# L1Demoscene.net
KiCad netlist of a schematic drawn in EAGLE
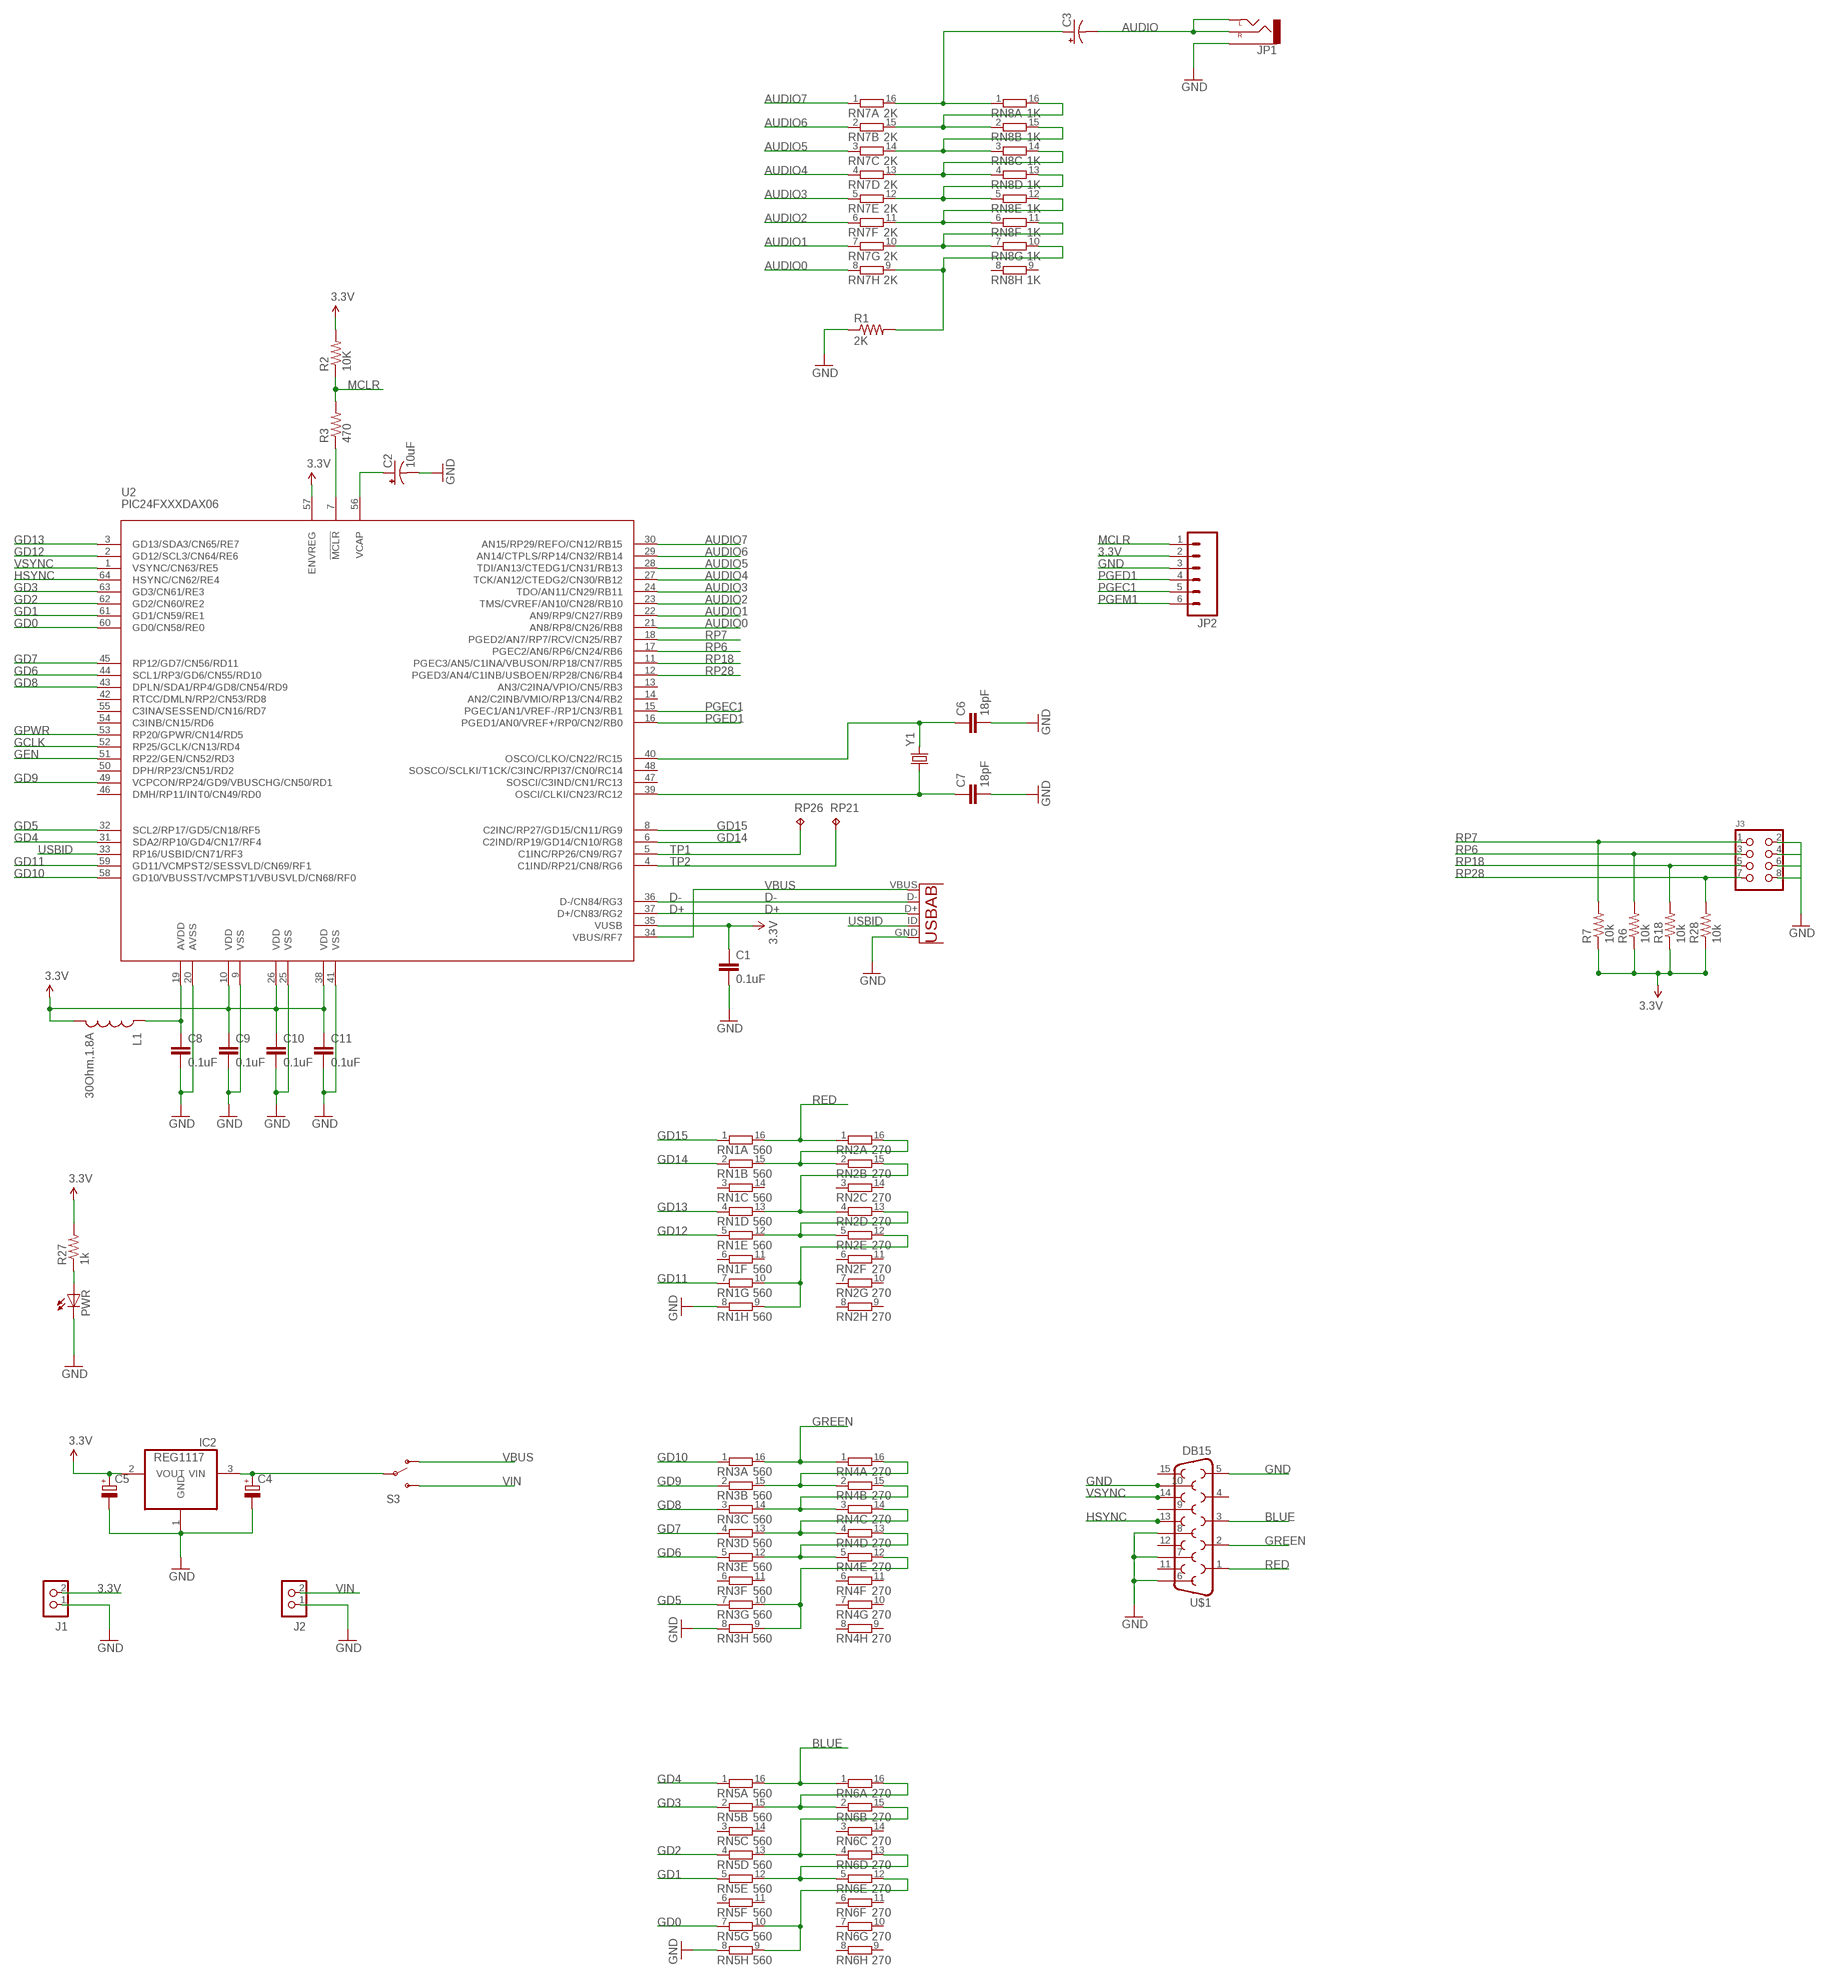
[diagram p0: schematic, sheet 1]

(export (version "E")
  (design (tool "Eeschema 10.0.6"))
  (components
    (comp (ref "C1")
      (value "0.1uF")
      (footprint "eagle-import:0603-CAP")
      (libsource (lib "eagle-import") (part "CAP0603-CAP"))
    )
    (comp (ref "C2")
      (value "10uF")
      (footprint "eagle-import:EIA3216")
      (libsource (lib "eagle-import") (part "CAP_POL1206"))
    )
    (comp (ref "C3")
      (value "CAP_POL1206")
      (footprint "eagle-import:EIA3216")
      (libsource (lib "eagle-import") (part "CAP_POL1206"))
    )
    (comp (ref "C4")
      (value "CAPACITOR_POL-SMC_A")
      (footprint "eagle-import:SMC_A")
      (libsource (lib "eagle-import") (part "CAPACITOR_POL-SMC_A"))
    )
    (comp (ref "C5")
      (value "CAPACITOR_POL-SMC_A")
      (footprint "eagle-import:SMC_A")
      (libsource (lib "eagle-import") (part "CAPACITOR_POL-SMC_A"))
    )
    (comp (ref "C6")
      (value "18pF")
      (footprint "eagle-import:0603-CAP")
      (libsource (lib "eagle-import") (part "CAP0603-CAP"))
    )
    (comp (ref "C7")
      (value "18pF")
      (footprint "eagle-import:0603-CAP")
      (libsource (lib "eagle-import") (part "CAP0603-CAP"))
    )
    (comp (ref "C8")
      (value "0.1uF")
      (footprint "eagle-import:0603-CAP")
      (libsource (lib "eagle-import") (part "CAP0603-CAP"))
    )
    (comp (ref "C9")
      (value "0.1uF")
      (footprint "eagle-import:0603-CAP")
      (libsource (lib "eagle-import") (part "CAP0603-CAP"))
    )
    (comp (ref "C10")
      (value "0.1uF")
      (footprint "eagle-import:0603-CAP")
      (libsource (lib "eagle-import") (part "CAP0603-CAP"))
    )
    (comp (ref "C11")
      (value "0.1uF")
      (footprint "eagle-import:0603-CAP")
      (libsource (lib "eagle-import") (part "CAP0603-CAP"))
    )
    (comp (ref "IC2")
      (value "REG1117")
      (footprint "eagle-import:SOT223")
      (libsource (lib "eagle-import") (part "REG1117"))
    )
    (comp (ref "J1")
      (value "CON_HEADER_1X02-PTH")
      (footprint "eagle-import:M1X2")
      (libsource (lib "eagle-import") (part "CON_HEADER_1X02-PTH"))
    )
    (comp (ref "J2")
      (value "CON_HEADER_1X02-PTH")
      (footprint "eagle-import:M1X2")
      (libsource (lib "eagle-import") (part "CON_HEADER_1X02-PTH"))
    )
    (comp (ref "J3")
      (value "CON_HEADER_2X04-PTH")
      (footprint "eagle-import:M2X4")
      (libsource (lib "eagle-import") (part "CON_HEADER_2X04-PTH"))
    )
    (comp (ref "JP1")
      (value "AUDIO-JACKPTH")
      (footprint "eagle-import:AUDIO-JACK")
      (libsource (lib "eagle-import") (part "AUDIO-JACKPTH"))
    )
    (comp (ref "JP2")
      (value "M06SIP")
      (footprint "eagle-import:1X06")
      (libsource (lib "eagle-import") (part "M06SIP"))
    )
    (comp (ref "L1")
      (value "30Ohm,1.8A")
      (footprint "eagle-import:C0402")
      (libsource (lib "eagle-import") (part "INDUCTOR0402"))
    )
    (comp (ref "PWR")
      (value "LED-0603")
      (footprint "eagle-import:LED-603")
      (libsource (lib "eagle-import") (part "LED-0603"))
    )
    (comp (ref "R1")
      (value "2K")
      (footprint "eagle-import:0603-RES")
      (libsource (lib "eagle-import") (part "RESISTOR0603-RES"))
    )
    (comp (ref "R2")
      (value "10K")
      (footprint "eagle-import:0603-RES")
      (libsource (lib "eagle-import") (part "RESISTOR0603-RES"))
    )
    (comp (ref "R3")
      (value "470")
      (footprint "eagle-import:0603-RES")
      (libsource (lib "eagle-import") (part "RESISTOR0603-RES"))
    )
    (comp (ref "R6")
      (value "10k")
      (footprint "eagle-import:0603-RES")
      (libsource (lib "eagle-import") (part "RESISTOR0603-RES"))
    )
    (comp (ref "R7")
      (value "10k")
      (footprint "eagle-import:0603-RES")
      (libsource (lib "eagle-import") (part "RESISTOR0603-RES"))
    )
    (comp (ref "R18")
      (value "10k")
      (footprint "eagle-import:0603-RES")
      (libsource (lib "eagle-import") (part "RESISTOR0603-RES"))
    )
    (comp (ref "R27")
      (value "1k")
      (footprint "eagle-import:0603-RES")
      (libsource (lib "eagle-import") (part "RESISTOR0603-RES"))
    )
    (comp (ref "R28")
      (value "10k")
      (footprint "eagle-import:0603-RES")
      (libsource (lib "eagle-import") (part "RESISTOR0603-RES"))
    )
    (comp (ref "RN1")
      (value "560")
      (footprint "eagle-import:EXB2HV")
      (libsource (lib "eagle-import") (part "8R-NEXB2HV"))
    )
    (comp (ref "RN2")
      (value "270")
      (footprint "eagle-import:EXB2HV")
      (libsource (lib "eagle-import") (part "8R-NEXB2HV"))
    )
    (comp (ref "RN3")
      (value "560")
      (footprint "eagle-import:EXB2HV")
      (libsource (lib "eagle-import") (part "8R-NEXB2HV"))
    )
    (comp (ref "RN4")
      (value "270")
      (footprint "eagle-import:EXB2HV")
      (libsource (lib "eagle-import") (part "8R-NEXB2HV"))
    )
    (comp (ref "RN5")
      (value "560")
      (footprint "eagle-import:EXB2HV")
      (libsource (lib "eagle-import") (part "8R-NEXB2HV"))
    )
    (comp (ref "RN6")
      (value "270")
      (footprint "eagle-import:EXB2HV")
      (libsource (lib "eagle-import") (part "8R-NEXB2HV"))
    )
    (comp (ref "RN7")
      (value "2K")
      (footprint "eagle-import:EXB2HV")
      (libsource (lib "eagle-import") (part "8R-NEXB2HV"))
    )
    (comp (ref "RN8")
      (value "1K")
      (footprint "eagle-import:EXB2HV")
      (libsource (lib "eagle-import") (part "8R-NEXB2HV"))
    )
    (comp (ref "RP21")
      (value "TPTP06R")
      (footprint "eagle-import:TP06R")
      (libsource (lib "eagle-import") (part "TPTP06R"))
    )
    (comp (ref "RP26")
      (value "TPTP06R")
      (footprint "eagle-import:TP06R")
      (libsource (lib "eagle-import") (part "TPTP06R"))
    )
    (comp (ref "S3")
      (value "SWITCH-SPDT-SMD-A")
      (footprint "eagle-import:SWITCH-SPST-SMD-A")
      (libsource (lib "eagle-import") (part "SWITCH-SPDT-SMD-A"))
    )
    (comp (ref "U$1")
      (value "DB15")
      (footprint "eagle-import:DB15")
      (libsource (lib "eagle-import") (part "DB15"))
    )
    (comp (ref "U2")
      (value "PIC24FXXXDAX06")
      (footprint "eagle-import:PIC24FXXX_TQFP64")
      (libsource (lib "eagle-import") (part "PIC24FXXXDAX06"))
    )
    (comp (ref "U3")
      (value "USB-AB")
      (footprint "eagle-import:USB-AB-MICRO-SMD")
      (libsource (lib "eagle-import") (part "USB-AB"))
    )
    (comp (ref "Y1")
      (value "CRYSTAL5X3")
      (footprint "eagle-import:CRYSTAL-SMD-5X3")
      (libsource (lib "eagle-import") (part "CRYSTAL5X3"))
    )
  )
  (nets
    (net (code "1") (name "/AUDIO") (class "Default")
      (node (ref "C3") (pin "C") (pinfunction "-_C") (pintype "passive"))
      (node (ref "JP1") (pin "RING") (pinfunction "RIGHT_RING") (pintype "bidirectional"))
      (node (ref "JP1") (pin "TIP") (pinfunction "LEFT_TIP") (pintype "bidirectional"))
    )
    (net (code "2") (name "/AUDIO0") (class "Default")
      (node (ref "RN7") (pin "8") (pinfunction "1_8") (pintype "passive"))
      (node (ref "U2") (pin "21") (pinfunction "AN8/RP8/CN26/RB8_21") (pintype "bidirectional"))
    )
    (net (code "3") (name "/AUDIO1") (class "Default")
      (node (ref "RN7") (pin "7") (pinfunction "1_7") (pintype "passive"))
      (node (ref "U2") (pin "22") (pinfunction "AN9/RP9/CN27/RB9_22") (pintype "bidirectional"))
    )
    (net (code "4") (name "/AUDIO2") (class "Default")
      (node (ref "RN7") (pin "6") (pinfunction "1_6") (pintype "passive"))
      (node (ref "U2") (pin "23") (pinfunction "TMS/CVREF/AN10/CN28/RB10_23") (pintype "bidirectional"))
    )
    (net (code "5") (name "/AUDIO3") (class "Default")
      (node (ref "RN7") (pin "5") (pinfunction "1_5") (pintype "passive"))
      (node (ref "U2") (pin "24") (pinfunction "TDO/AN11/CN29/RB11_24") (pintype "bidirectional"))
    )
    (net (code "6") (name "/AUDIO4") (class "Default")
      (node (ref "RN7") (pin "4") (pinfunction "1_4") (pintype "passive"))
      (node (ref "U2") (pin "27") (pinfunction "TCK/AN12/CTEDG2/CN30/RB12_27") (pintype "bidirectional"))
    )
    (net (code "7") (name "/AUDIO5") (class "Default")
      (node (ref "RN7") (pin "3") (pinfunction "1_3") (pintype "passive"))
      (node (ref "U2") (pin "28") (pinfunction "TDI/AN13/CTEDG1/CN31/RB13_28") (pintype "bidirectional"))
    )
    (net (code "8") (name "/AUDIO6") (class "Default")
      (node (ref "RN7") (pin "2") (pinfunction "1_2") (pintype "passive"))
      (node (ref "U2") (pin "29") (pinfunction "AN14/CTPLS/RP14/CN32/RB14_29") (pintype "bidirectional"))
    )
    (net (code "9") (name "/AUDIO7") (class "Default")
      (node (ref "RN7") (pin "1") (pinfunction "1_1") (pintype "passive"))
      (node (ref "U2") (pin "30") (pinfunction "AN15/RP29/REFO/CN12/RB15_30") (pintype "bidirectional"))
    )
    (net (code "10") (name "/BLUE") (class "Default")
      (node (ref "RN5") (pin "16") (pinfunction "2_16") (pintype "passive"))
      (node (ref "RN6") (pin "1") (pinfunction "1_1") (pintype "passive"))
      (node (ref "U$1") (pin "3") (pinfunction "3_3") (pintype "passive"))
    )
    (net (code "11") (name "/D+") (class "Default")
      (node (ref "U2") (pin "37") (pinfunction "D+/CN83/RG2_37") (pintype "bidirectional"))
      (node (ref "U3") (pin "D+") (pinfunction "D+_D+") (pintype "bidirectional"))
    )
    (net (code "12") (name "/D-") (class "Default")
      (node (ref "U2") (pin "36") (pinfunction "D-/CN84/RG3_36") (pintype "bidirectional"))
      (node (ref "U3") (pin "D-") (pinfunction "D-_D-") (pintype "bidirectional"))
    )
    (net (code "13") (name "/GCLK") (class "Default")
      (node (ref "U2") (pin "52") (pinfunction "RP25/GCLK/CN13/RD4_52") (pintype "bidirectional"))
    )
    (net (code "14") (name "/GD0") (class "Default")
      (node (ref "RN5") (pin "7") (pinfunction "1_7") (pintype "passive"))
      (node (ref "U2") (pin "60") (pinfunction "GD0/CN58/RE0_60") (pintype "bidirectional"))
    )
    (net (code "15") (name "/GD1") (class "Default")
      (node (ref "RN5") (pin "5") (pinfunction "1_5") (pintype "passive"))
      (node (ref "U2") (pin "61") (pinfunction "GD1/CN59/RE1_61") (pintype "bidirectional"))
    )
    (net (code "16") (name "/GD2") (class "Default")
      (node (ref "RN5") (pin "4") (pinfunction "1_4") (pintype "passive"))
      (node (ref "U2") (pin "62") (pinfunction "GD2/CN60/RE2_62") (pintype "bidirectional"))
    )
    (net (code "17") (name "/GD3") (class "Default")
      (node (ref "RN5") (pin "2") (pinfunction "1_2") (pintype "passive"))
      (node (ref "U2") (pin "63") (pinfunction "GD3/CN61/RE3_63") (pintype "bidirectional"))
    )
    (net (code "18") (name "/GD4") (class "Default")
      (node (ref "RN5") (pin "1") (pinfunction "1_1") (pintype "passive"))
      (node (ref "U2") (pin "31") (pinfunction "SDA2/RP10/GD4/CN17/RF4_31") (pintype "bidirectional"))
    )
    (net (code "19") (name "/GD5") (class "Default")
      (node (ref "RN3") (pin "7") (pinfunction "1_7") (pintype "passive"))
      (node (ref "U2") (pin "32") (pinfunction "SCL2/RP17/GD5/CN18/RF5_32") (pintype "bidirectional"))
    )
    (net (code "20") (name "/GD6") (class "Default")
      (node (ref "RN3") (pin "5") (pinfunction "1_5") (pintype "passive"))
      (node (ref "U2") (pin "44") (pinfunction "SCL1/RP3/GD6/CN55/RD10_44") (pintype "bidirectional"))
    )
    (net (code "21") (name "/GD7") (class "Default")
      (node (ref "RN3") (pin "4") (pinfunction "1_4") (pintype "passive"))
      (node (ref "U2") (pin "45") (pinfunction "RP12/GD7/CN56/RD11_45") (pintype "bidirectional"))
    )
    (net (code "22") (name "/GD8") (class "Default")
      (node (ref "RN3") (pin "3") (pinfunction "1_3") (pintype "passive"))
      (node (ref "U2") (pin "43") (pinfunction "DPLN/SDA1/RP4/GD8/CN54/RD9_43") (pintype "bidirectional"))
    )
    (net (code "23") (name "/GD9") (class "Default")
      (node (ref "RN3") (pin "2") (pinfunction "1_2") (pintype "passive"))
      (node (ref "U2") (pin "49") (pinfunction "VCPCON/RP24/GD9/VBUSCHG/CN50/RD1_49") (pintype "bidirectional"))
    )
    (net (code "24") (name "/GD10") (class "Default")
      (node (ref "RN3") (pin "1") (pinfunction "1_1") (pintype "passive"))
      (node (ref "U2") (pin "58") (pinfunction "GD10/VBUSST/VCMPST1/VBUSVLD/CN68/RF0_58") (pintype "bidirectional"))
    )
    (net (code "25") (name "/GD11") (class "Default")
      (node (ref "RN1") (pin "7") (pinfunction "1_7") (pintype "passive"))
      (node (ref "U2") (pin "59") (pinfunction "GD11/VCMPST2/SESSVLD/CN69/RF1_59") (pintype "bidirectional"))
    )
    (net (code "26") (name "/GD12") (class "Default")
      (node (ref "RN1") (pin "5") (pinfunction "1_5") (pintype "passive"))
      (node (ref "U2") (pin "2") (pinfunction "GD12/SCL3/CN64/RE6_2") (pintype "bidirectional"))
    )
    (net (code "27") (name "/GD13") (class "Default")
      (node (ref "RN1") (pin "4") (pinfunction "1_4") (pintype "passive"))
      (node (ref "U2") (pin "3") (pinfunction "GD13/SDA3/CN65/RE7_3") (pintype "bidirectional"))
    )
    (net (code "28") (name "/GD14") (class "Default")
      (node (ref "RN1") (pin "2") (pinfunction "1_2") (pintype "passive"))
      (node (ref "U2") (pin "6") (pinfunction "C2IND/RP19/GD14/CN10/RG8_6") (pintype "bidirectional"))
    )
    (net (code "29") (name "/GD15") (class "Default")
      (node (ref "RN1") (pin "1") (pinfunction "1_1") (pintype "passive"))
      (node (ref "U2") (pin "8") (pinfunction "C2INC/RP27/GD15/CN11/RG9_8") (pintype "bidirectional"))
    )
    (net (code "30") (name "/GEN") (class "Default")
      (node (ref "U2") (pin "51") (pinfunction "RP22/GEN/CN52/RD3_51") (pintype "bidirectional"))
    )
    (net (code "31") (name "/GPWR") (class "Default")
      (node (ref "U2") (pin "53") (pinfunction "RP20/GPWR/CN14/RD5_53") (pintype "bidirectional"))
    )
    (net (code "32") (name "/GREEN") (class "Default")
      (node (ref "RN3") (pin "16") (pinfunction "2_16") (pintype "passive"))
      (node (ref "RN4") (pin "1") (pinfunction "1_1") (pintype "passive"))
      (node (ref "U$1") (pin "2") (pinfunction "2_2") (pintype "passive"))
    )
    (net (code "33") (name "/HSYNC") (class "Default")
      (node (ref "U$1") (pin "13") (pinfunction "13_13") (pintype "passive"))
      (node (ref "U2") (pin "64") (pinfunction "HSYNC/CN62/RE4_64") (pintype "bidirectional"))
    )
    (net (code "34") (name "/MCLR") (class "Default")
      (node (ref "JP2") (pin "1") (pinfunction "1_1") (pintype "passive"))
      (node (ref "R2") (pin "1") (pinfunction "1_1") (pintype "passive"))
      (node (ref "R3") (pin "2") (pinfunction "2_2") (pintype "passive"))
    )
    (net (code "35") (name "/PGEC1") (class "Default")
      (node (ref "JP2") (pin "5") (pinfunction "5_5") (pintype "passive"))
      (node (ref "U2") (pin "15") (pinfunction "PGEC1/AN1/VREF-/RP1/CN3/RB1_15") (pintype "bidirectional"))
    )
    (net (code "36") (name "/PGED1") (class "Default")
      (node (ref "JP2") (pin "4") (pinfunction "4_4") (pintype "passive"))
      (node (ref "U2") (pin "16") (pinfunction "PGED1/AN0/VREF+/RP0/CN2/RB0_16") (pintype "bidirectional"))
    )
    (net (code "37") (name "/PGEM1") (class "Default")
      (node (ref "JP2") (pin "6") (pinfunction "6_6") (pintype "passive"))
    )
    (net (code "38") (name "/RED") (class "Default")
      (node (ref "RN1") (pin "16") (pinfunction "2_16") (pintype "passive"))
      (node (ref "RN2") (pin "1") (pinfunction "1_1") (pintype "passive"))
      (node (ref "U$1") (pin "1") (pinfunction "1_1") (pintype "passive"))
    )
    (net (code "39") (name "/RP6") (class "Default")
      (node (ref "J3") (pin "3") (pinfunction "P$3_3") (pintype "passive"))
      (node (ref "R6") (pin "2") (pinfunction "2_2") (pintype "passive"))
      (node (ref "U2") (pin "17") (pinfunction "PGEC2/AN6/RP6/CN24/RB6_17") (pintype "bidirectional"))
    )
    (net (code "40") (name "/RP7") (class "Default")
      (node (ref "J3") (pin "1") (pinfunction "P$1_1") (pintype "passive"))
      (node (ref "R7") (pin "2") (pinfunction "2_2") (pintype "passive"))
      (node (ref "U2") (pin "18") (pinfunction "PGED2/AN7/RP7/RCV/CN25/RB7_18") (pintype "bidirectional"))
    )
    (net (code "41") (name "/RP18") (class "Default")
      (node (ref "J3") (pin "5") (pinfunction "P$5_5") (pintype "passive"))
      (node (ref "R18") (pin "2") (pinfunction "2_2") (pintype "passive"))
      (node (ref "U2") (pin "11") (pinfunction "PGEC3/AN5/C1INA/VBUSON/RP18/CN7/RB5_11") (pintype "bidirectional"))
    )
    (net (code "42") (name "/RP28") (class "Default")
      (node (ref "J3") (pin "7") (pinfunction "P$7_7") (pintype "passive"))
      (node (ref "R28") (pin "2") (pinfunction "2_2") (pintype "passive"))
      (node (ref "U2") (pin "12") (pinfunction "PGED3/AN4/C1INB/USBOEN/RP28/CN6/RB4_12") (pintype "bidirectional"))
    )
    (net (code "43") (name "/TP1") (class "Default")
      (node (ref "RP26") (pin "TP") (pinfunction "TP_TP") (pintype "input"))
      (node (ref "U2") (pin "5") (pinfunction "C1INC/RP26/CN9/RG7_5") (pintype "bidirectional"))
    )
    (net (code "44") (name "/TP2") (class "Default")
      (node (ref "RP21") (pin "TP") (pinfunction "TP_TP") (pintype "input"))
      (node (ref "U2") (pin "4") (pinfunction "C1IND/RP21/CN8/RG6_4") (pintype "bidirectional"))
    )
    (net (code "45") (name "/USBID") (class "Default")
      (node (ref "U2") (pin "33") (pinfunction "RP16/USBID/CN71/RF3_33") (pintype "bidirectional"))
      (node (ref "U3") (pin "ID") (pinfunction "USBID_ID") (pintype "bidirectional"))
    )
    (net (code "46") (name "/VBUS") (class "Default")
      (node (ref "S3") (pin "1") (pinfunction "O_1") (pintype "passive"))
      (node (ref "U2") (pin "34") (pinfunction "VBUS/RF7_34") (pintype "input"))
      (node (ref "U3") (pin "VBUS") (pinfunction "VBUS_VBUS") (pintype "bidirectional"))
    )
    (net (code "47") (name "/VIN") (class "Default")
      (node (ref "J2") (pin "2") (pinfunction "2_2") (pintype "passive"))
      (node (ref "S3") (pin "3") (pinfunction "S_3") (pintype "passive"))
    )
    (net (code "48") (name "/VSYNC") (class "Default")
      (node (ref "U$1") (pin "14") (pinfunction "14_14") (pintype "passive"))
      (node (ref "U2") (pin "1") (pinfunction "VSYNC/CN63/RE5_1") (pintype "bidirectional"))
    )
    (net (code "49") (name "3.3V") (class "Default")
      (node (ref "C1") (pin "1") (pinfunction "1_1") (pintype "passive"))
      (node (ref "C10") (pin "1") (pinfunction "1_1") (pintype "passive"))
      (node (ref "C11") (pin "1") (pinfunction "1_1") (pintype "passive"))
      (node (ref "C5") (pin "+") (pinfunction "+_+") (pintype "passive"))
      (node (ref "C9") (pin "1") (pinfunction "1_1") (pintype "passive"))
      (node (ref "IC2") (pin "2") (pinfunction "VOUT_2") (pintype "output"))
      (node (ref "J1") (pin "2") (pinfunction "2_2") (pintype "passive"))
      (node (ref "JP2") (pin "2") (pinfunction "2_2") (pintype "passive"))
      (node (ref "L1") (pin "2") (pinfunction "2_2") (pintype "passive"))
      (node (ref "R18") (pin "1") (pinfunction "1_1") (pintype "passive"))
      (node (ref "R2") (pin "2") (pinfunction "2_2") (pintype "passive"))
      (node (ref "R27") (pin "2") (pinfunction "2_2") (pintype "passive"))
      (node (ref "R28") (pin "1") (pinfunction "1_1") (pintype "passive"))
      (node (ref "R6") (pin "1") (pinfunction "1_1") (pintype "passive"))
      (node (ref "R7") (pin "1") (pinfunction "1_1") (pintype "passive"))
      (node (ref "U2") (pin "10") (pinfunction "VDD_10") (pintype "power_in"))
      (node (ref "U2") (pin "26") (pinfunction "VDD_26") (pintype "power_in"))
      (node (ref "U2") (pin "35") (pinfunction "VUSB_35") (pintype "power_in"))
      (node (ref "U2") (pin "38") (pinfunction "VDD_38") (pintype "power_in"))
      (node (ref "U2") (pin "57") (pinfunction "ENVREG_57") (pintype "input"))
    )
    (net (code "50") (name "GND") (class "Default")
      (node (ref "C1") (pin "2") (pinfunction "2_2") (pintype "passive"))
      (node (ref "C10") (pin "2") (pinfunction "2_2") (pintype "passive"))
      (node (ref "C11") (pin "2") (pinfunction "2_2") (pintype "passive"))
      (node (ref "C2") (pin "C") (pinfunction "-_C") (pintype "passive"))
      (node (ref "C4") (pin "-") (pinfunction "-_-") (pintype "passive"))
      (node (ref "C5") (pin "-") (pinfunction "-_-") (pintype "passive"))
      (node (ref "C6") (pin "2") (pinfunction "2_2") (pintype "passive"))
      (node (ref "C7") (pin "2") (pinfunction "2_2") (pintype "passive"))
      (node (ref "C8") (pin "2") (pinfunction "2_2") (pintype "passive"))
      (node (ref "C9") (pin "2") (pinfunction "2_2") (pintype "passive"))
      (node (ref "IC2") (pin "1") (pinfunction "GND_1") (pintype "power_in"))
      (node (ref "J1") (pin "1") (pinfunction "1_1") (pintype "passive"))
      (node (ref "J2") (pin "1") (pinfunction "1_1") (pintype "passive"))
      (node (ref "J3") (pin "2") (pinfunction "P$2_2") (pintype "passive"))
      (node (ref "J3") (pin "4") (pinfunction "P$4_4") (pintype "passive"))
      (node (ref "J3") (pin "6") (pinfunction "P$6_6") (pintype "passive"))
      (node (ref "J3") (pin "8") (pinfunction "P$8_8") (pintype "passive"))
      (node (ref "JP1") (pin "SLEEVE") (pinfunction "SLEEVE_SLEEVE") (pintype "bidirectional"))
      (node (ref "JP2") (pin "3") (pinfunction "3_3") (pintype "passive"))
      (node (ref "PWR") (pin "C") (pinfunction "C_C") (pintype "passive"))
      (node (ref "R1") (pin "1") (pinfunction "1_1") (pintype "passive"))
      (node (ref "RN1") (pin "8") (pinfunction "1_8") (pintype "passive"))
      (node (ref "RN3") (pin "8") (pinfunction "1_8") (pintype "passive"))
      (node (ref "RN5") (pin "8") (pinfunction "1_8") (pintype "passive"))
      (node (ref "U$1") (pin "10") (pinfunction "10_10") (pintype "passive"))
      (node (ref "U$1") (pin "5") (pinfunction "5_5") (pintype "passive"))
      (node (ref "U$1") (pin "6") (pinfunction "6_6") (pintype "passive"))
      (node (ref "U$1") (pin "7") (pinfunction "7_7") (pintype "passive"))
      (node (ref "U$1") (pin "8") (pinfunction "8_8") (pintype "passive"))
      (node (ref "U2") (pin "20") (pinfunction "AVSS_20") (pintype "power_in"))
      (node (ref "U2") (pin "25") (pinfunction "VSS_25") (pintype "power_in"))
      (node (ref "U2") (pin "41") (pinfunction "VSS_41") (pintype "power_in"))
      (node (ref "U2") (pin "9") (pinfunction "VSS_9") (pintype "power_in"))
      (node (ref "U3") (pin "GND") (pinfunction "GND_GND") (pintype "bidirectional"))
    )
    (net (code "51") (name "Net-(C2-+)") (class "Default")
      (node (ref "C2") (pin "A") (pinfunction "+_A") (pintype "passive"))
      (node (ref "U2") (pin "56") (pinfunction "VCAP_56") (pintype "power_in"))
    )
    (net (code "52") (name "Net-(C3-+)") (class "Default")
      (node (ref "C3") (pin "A") (pinfunction "+_A") (pintype "passive"))
      (node (ref "RN7") (pin "16") (pinfunction "2_16") (pintype "passive"))
      (node (ref "RN8") (pin "1") (pinfunction "1_1") (pintype "passive"))
    )
    (net (code "53") (name "Net-(IC2-VIN)") (class "Default")
      (node (ref "C4") (pin "+") (pinfunction "+_+") (pintype "passive"))
      (node (ref "IC2") (pin "3") (pinfunction "VIN_3") (pintype "input"))
      (node (ref "S3") (pin "2") (pinfunction "P_2") (pintype "passive"))
    )
    (net (code "54") (name "Net-(PWR-PadA)") (class "Default")
      (node (ref "PWR") (pin "A") (pinfunction "A_A") (pintype "passive"))
      (node (ref "R27") (pin "1") (pinfunction "1_1") (pintype "passive"))
    )
    (net (code "55") (name "Net-(RN1B-2)") (class "Default")
      (node (ref "RN1") (pin "15") (pinfunction "2_15") (pintype "passive"))
      (node (ref "RN2") (pin "16") (pinfunction "2_16") (pintype "passive"))
      (node (ref "RN2") (pin "2") (pinfunction "1_2") (pintype "passive"))
    )
    (net (code "56") (name "Net-(RN1D-2)") (class "Default")
      (node (ref "RN1") (pin "13") (pinfunction "2_13") (pintype "passive"))
      (node (ref "RN2") (pin "15") (pinfunction "2_15") (pintype "passive"))
      (node (ref "RN2") (pin "4") (pinfunction "1_4") (pintype "passive"))
    )
    (net (code "57") (name "Net-(RN1E-2)") (class "Default")
      (node (ref "RN1") (pin "12") (pinfunction "2_12") (pintype "passive"))
      (node (ref "RN2") (pin "13") (pinfunction "2_13") (pintype "passive"))
      (node (ref "RN2") (pin "5") (pinfunction "1_5") (pintype "passive"))
    )
    (net (code "58") (name "Net-(RN1G-2)") (class "Default")
      (node (ref "RN1") (pin "10") (pinfunction "2_10") (pintype "passive"))
      (node (ref "RN1") (pin "9") (pinfunction "2_9") (pintype "passive"))
      (node (ref "RN2") (pin "12") (pinfunction "2_12") (pintype "passive"))
    )
    (net (code "59") (name "Net-(RN3B-2)") (class "Default")
      (node (ref "RN3") (pin "15") (pinfunction "2_15") (pintype "passive"))
      (node (ref "RN4") (pin "16") (pinfunction "2_16") (pintype "passive"))
      (node (ref "RN4") (pin "2") (pinfunction "1_2") (pintype "passive"))
    )
    (net (code "60") (name "Net-(RN3C-2)") (class "Default")
      (node (ref "RN3") (pin "14") (pinfunction "2_14") (pintype "passive"))
      (node (ref "RN4") (pin "15") (pinfunction "2_15") (pintype "passive"))
      (node (ref "RN4") (pin "3") (pinfunction "1_3") (pintype "passive"))
    )
    (net (code "61") (name "Net-(RN3D-2)") (class "Default")
      (node (ref "RN3") (pin "13") (pinfunction "2_13") (pintype "passive"))
      (node (ref "RN4") (pin "14") (pinfunction "2_14") (pintype "passive"))
      (node (ref "RN4") (pin "4") (pinfunction "1_4") (pintype "passive"))
    )
    (net (code "62") (name "Net-(RN3E-2)") (class "Default")
      (node (ref "RN3") (pin "12") (pinfunction "2_12") (pintype "passive"))
      (node (ref "RN4") (pin "13") (pinfunction "2_13") (pintype "passive"))
      (node (ref "RN4") (pin "5") (pinfunction "1_5") (pintype "passive"))
    )
    (net (code "63") (name "Net-(RN3G-2)") (class "Default")
      (node (ref "RN3") (pin "10") (pinfunction "2_10") (pintype "passive"))
      (node (ref "RN3") (pin "9") (pinfunction "2_9") (pintype "passive"))
      (node (ref "RN4") (pin "12") (pinfunction "2_12") (pintype "passive"))
    )
    (net (code "64") (name "Net-(RN5B-2)") (class "Default")
      (node (ref "RN5") (pin "15") (pinfunction "2_15") (pintype "passive"))
      (node (ref "RN6") (pin "16") (pinfunction "2_16") (pintype "passive"))
      (node (ref "RN6") (pin "2") (pinfunction "1_2") (pintype "passive"))
    )
    (net (code "65") (name "Net-(RN5D-2)") (class "Default")
      (node (ref "RN5") (pin "13") (pinfunction "2_13") (pintype "passive"))
      (node (ref "RN6") (pin "15") (pinfunction "2_15") (pintype "passive"))
      (node (ref "RN6") (pin "4") (pinfunction "1_4") (pintype "passive"))
    )
    (net (code "66") (name "Net-(RN5E-2)") (class "Default")
      (node (ref "RN5") (pin "12") (pinfunction "2_12") (pintype "passive"))
      (node (ref "RN6") (pin "13") (pinfunction "2_13") (pintype "passive"))
      (node (ref "RN6") (pin "5") (pinfunction "1_5") (pintype "passive"))
    )
    (net (code "67") (name "Net-(RN5G-2)") (class "Default")
      (node (ref "RN5") (pin "10") (pinfunction "2_10") (pintype "passive"))
      (node (ref "RN5") (pin "9") (pinfunction "2_9") (pintype "passive"))
      (node (ref "RN6") (pin "12") (pinfunction "2_12") (pintype "passive"))
    )
    (net (code "68") (name "Net-(RN7B-2)") (class "Default")
      (node (ref "RN7") (pin "15") (pinfunction "2_15") (pintype "passive"))
      (node (ref "RN8") (pin "16") (pinfunction "2_16") (pintype "passive"))
      (node (ref "RN8") (pin "2") (pinfunction "1_2") (pintype "passive"))
    )
    (net (code "69") (name "Net-(RN7C-2)") (class "Default")
      (node (ref "RN7") (pin "14") (pinfunction "2_14") (pintype "passive"))
      (node (ref "RN8") (pin "15") (pinfunction "2_15") (pintype "passive"))
      (node (ref "RN8") (pin "3") (pinfunction "1_3") (pintype "passive"))
    )
    (net (code "70") (name "Net-(RN7D-2)") (class "Default")
      (node (ref "RN7") (pin "13") (pinfunction "2_13") (pintype "passive"))
      (node (ref "RN8") (pin "14") (pinfunction "2_14") (pintype "passive"))
      (node (ref "RN8") (pin "4") (pinfunction "1_4") (pintype "passive"))
    )
    (net (code "71") (name "Net-(RN7E-2)") (class "Default")
      (node (ref "RN7") (pin "12") (pinfunction "2_12") (pintype "passive"))
      (node (ref "RN8") (pin "13") (pinfunction "2_13") (pintype "passive"))
      (node (ref "RN8") (pin "5") (pinfunction "1_5") (pintype "passive"))
    )
    (net (code "72") (name "Net-(RN7F-2)") (class "Default")
      (node (ref "RN7") (pin "11") (pinfunction "2_11") (pintype "passive"))
      (node (ref "RN8") (pin "12") (pinfunction "2_12") (pintype "passive"))
      (node (ref "RN8") (pin "6") (pinfunction "1_6") (pintype "passive"))
    )
    (net (code "73") (name "Net-(RN7G-2)") (class "Default")
      (node (ref "RN7") (pin "10") (pinfunction "2_10") (pintype "passive"))
      (node (ref "RN8") (pin "11") (pinfunction "2_11") (pintype "passive"))
      (node (ref "RN8") (pin "7") (pinfunction "1_7") (pintype "passive"))
    )
    (net (code "74") (name "Net-(RN7H-2)") (class "Default")
      (node (ref "R1") (pin "2") (pinfunction "2_2") (pintype "passive"))
      (node (ref "RN7") (pin "9") (pinfunction "2_9") (pintype "passive"))
      (node (ref "RN8") (pin "10") (pinfunction "2_10") (pintype "passive"))
    )
    (net (code "75") (name "Net-(U2-AVDD)") (class "Default")
      (node (ref "C8") (pin "1") (pinfunction "1_1") (pintype "passive"))
      (node (ref "L1") (pin "1") (pinfunction "1_1") (pintype "passive"))
      (node (ref "U2") (pin "19") (pinfunction "AVDD_19") (pintype "power_in"))
    )
    (net (code "76") (name "Net-(U2-OSCI{slash}CLKI{slash}CN23{slash}RC12)") (class "Default")
      (node (ref "C7") (pin "1") (pinfunction "1_1") (pintype "passive"))
      (node (ref "U2") (pin "39") (pinfunction "OSCI/CLKI/CN23/RC12_39") (pintype "bidirectional"))
      (node (ref "Y1") (pin "1") (pinfunction "1_1") (pintype "passive"))
    )
    (net (code "77") (name "Net-(U2-OSCO{slash}CLKO{slash}CN22{slash}RC15)") (class "Default")
      (node (ref "C6") (pin "1") (pinfunction "1_1") (pintype "passive"))
      (node (ref "U2") (pin "40") (pinfunction "OSCO/CLKO/CN22/RC15_40") (pintype "bidirectional"))
      (node (ref "Y1") (pin "3") (pinfunction "2_3") (pintype "passive"))
    )
    (net (code "78") (name "Net-(U2-~{MCLR})") (class "Default")
      (node (ref "R3") (pin "1") (pinfunction "1_1") (pintype "passive"))
      (node (ref "U2") (pin "7") (pinfunction "~{MCLR}_7") (pintype "input"))
    )
    (net (code "79") (name "unconnected-(RN1C-1-Pad3)") (class "Default")
      (node (ref "RN1") (pin "3") (pinfunction "1_3") (pintype "passive"))
    )
    (net (code "80") (name "unconnected-(RN1C-2-Pad14)") (class "Default")
      (node (ref "RN1") (pin "14") (pinfunction "2_14") (pintype "passive"))
    )
    (net (code "81") (name "unconnected-(RN1F-1-Pad6)") (class "Default")
      (node (ref "RN1") (pin "6") (pinfunction "1_6") (pintype "passive"))
    )
    (net (code "82") (name "unconnected-(RN1F-2-Pad11)") (class "Default")
      (node (ref "RN1") (pin "11") (pinfunction "2_11") (pintype "passive"))
    )
    (net (code "83") (name "unconnected-(RN2C-1-Pad3)") (class "Default")
      (node (ref "RN2") (pin "3") (pinfunction "1_3") (pintype "passive"))
    )
    (net (code "84") (name "unconnected-(RN2C-2-Pad14)") (class "Default")
      (node (ref "RN2") (pin "14") (pinfunction "2_14") (pintype "passive"))
    )
    (net (code "85") (name "unconnected-(RN2F-1-Pad6)") (class "Default")
      (node (ref "RN2") (pin "6") (pinfunction "1_6") (pintype "passive"))
    )
    (net (code "86") (name "unconnected-(RN2F-2-Pad11)") (class "Default")
      (node (ref "RN2") (pin "11") (pinfunction "2_11") (pintype "passive"))
    )
    (net (code "87") (name "unconnected-(RN2G-1-Pad7)") (class "Default")
      (node (ref "RN2") (pin "7") (pinfunction "1_7") (pintype "passive"))
    )
    (net (code "88") (name "unconnected-(RN2G-2-Pad10)") (class "Default")
      (node (ref "RN2") (pin "10") (pinfunction "2_10") (pintype "passive"))
    )
    (net (code "89") (name "unconnected-(RN2H-1-Pad8)") (class "Default")
      (node (ref "RN2") (pin "8") (pinfunction "1_8") (pintype "passive"))
    )
    (net (code "90") (name "unconnected-(RN2H-2-Pad9)") (class "Default")
      (node (ref "RN2") (pin "9") (pinfunction "2_9") (pintype "passive"))
    )
    (net (code "91") (name "unconnected-(RN3F-1-Pad6)") (class "Default")
      (node (ref "RN3") (pin "6") (pinfunction "1_6") (pintype "passive"))
    )
    (net (code "92") (name "unconnected-(RN3F-2-Pad11)") (class "Default")
      (node (ref "RN3") (pin "11") (pinfunction "2_11") (pintype "passive"))
    )
    (net (code "93") (name "unconnected-(RN4F-1-Pad6)") (class "Default")
      (node (ref "RN4") (pin "6") (pinfunction "1_6") (pintype "passive"))
    )
    (net (code "94") (name "unconnected-(RN4F-2-Pad11)") (class "Default")
      (node (ref "RN4") (pin "11") (pinfunction "2_11") (pintype "passive"))
    )
    (net (code "95") (name "unconnected-(RN4G-1-Pad7)") (class "Default")
      (node (ref "RN4") (pin "7") (pinfunction "1_7") (pintype "passive"))
    )
    (net (code "96") (name "unconnected-(RN4G-2-Pad10)") (class "Default")
      (node (ref "RN4") (pin "10") (pinfunction "2_10") (pintype "passive"))
    )
    (net (code "97") (name "unconnected-(RN4H-1-Pad8)") (class "Default")
      (node (ref "RN4") (pin "8") (pinfunction "1_8") (pintype "passive"))
    )
    (net (code "98") (name "unconnected-(RN4H-2-Pad9)") (class "Default")
      (node (ref "RN4") (pin "9") (pinfunction "2_9") (pintype "passive"))
    )
    (net (code "99") (name "unconnected-(RN5C-1-Pad3)") (class "Default")
      (node (ref "RN5") (pin "3") (pinfunction "1_3") (pintype "passive"))
    )
    (net (code "100") (name "unconnected-(RN5C-2-Pad14)") (class "Default")
      (node (ref "RN5") (pin "14") (pinfunction "2_14") (pintype "passive"))
    )
    (net (code "101") (name "unconnected-(RN5F-1-Pad6)") (class "Default")
      (node (ref "RN5") (pin "6") (pinfunction "1_6") (pintype "passive"))
    )
    (net (code "102") (name "unconnected-(RN5F-2-Pad11)") (class "Default")
      (node (ref "RN5") (pin "11") (pinfunction "2_11") (pintype "passive"))
    )
    (net (code "103") (name "unconnected-(RN6C-1-Pad3)") (class "Default")
      (node (ref "RN6") (pin "3") (pinfunction "1_3") (pintype "passive"))
    )
    (net (code "104") (name "unconnected-(RN6C-2-Pad14)") (class "Default")
      (node (ref "RN6") (pin "14") (pinfunction "2_14") (pintype "passive"))
    )
    (net (code "105") (name "unconnected-(RN6F-1-Pad6)") (class "Default")
      (node (ref "RN6") (pin "6") (pinfunction "1_6") (pintype "passive"))
    )
    (net (code "106") (name "unconnected-(RN6F-2-Pad11)") (class "Default")
      (node (ref "RN6") (pin "11") (pinfunction "2_11") (pintype "passive"))
    )
    (net (code "107") (name "unconnected-(RN6G-1-Pad7)") (class "Default")
      (node (ref "RN6") (pin "7") (pinfunction "1_7") (pintype "passive"))
    )
    (net (code "108") (name "unconnected-(RN6G-2-Pad10)") (class "Default")
      (node (ref "RN6") (pin "10") (pinfunction "2_10") (pintype "passive"))
    )
    (net (code "109") (name "unconnected-(RN6H-1-Pad8)") (class "Default")
      (node (ref "RN6") (pin "8") (pinfunction "1_8") (pintype "passive"))
    )
    (net (code "110") (name "unconnected-(RN6H-2-Pad9)") (class "Default")
      (node (ref "RN6") (pin "9") (pinfunction "2_9") (pintype "passive"))
    )
    (net (code "111") (name "unconnected-(RN8H-1-Pad8)") (class "Default")
      (node (ref "RN8") (pin "8") (pinfunction "1_8") (pintype "passive"))
    )
    (net (code "112") (name "unconnected-(RN8H-2-Pad9)") (class "Default")
      (node (ref "RN8") (pin "9") (pinfunction "2_9") (pintype "passive"))
    )
    (net (code "113") (name "unconnected-(U$1-Pad4)") (class "Default")
      (node (ref "U$1") (pin "4") (pinfunction "4_4") (pintype "passive"))
    )
    (net (code "114") (name "unconnected-(U$1-Pad9)") (class "Default")
      (node (ref "U$1") (pin "9") (pinfunction "9_9") (pintype "passive"))
    )
    (net (code "115") (name "unconnected-(U$1-Pad11)") (class "Default")
      (node (ref "U$1") (pin "11") (pinfunction "11_11") (pintype "passive"))
    )
    (net (code "116") (name "unconnected-(U$1-Pad12)") (class "Default")
      (node (ref "U$1") (pin "12") (pinfunction "12_12") (pintype "passive"))
    )
    (net (code "117") (name "unconnected-(U$1-Pad15)") (class "Default")
      (node (ref "U$1") (pin "15") (pinfunction "15_15") (pintype "passive"))
    )
    (net (code "118") (name "unconnected-(U2-AN2{slash}C2INB{slash}VMIO{slash}RP13{slash}CN4{slash}RB2-Pad14)") (class "Default")
      (node (ref "U2") (pin "14") (pinfunction "AN2/C2INB/VMIO/RP13/CN4/RB2_14") (pintype "bidirectional"))
    )
    (net (code "119") (name "unconnected-(U2-AN3{slash}C2INA{slash}VPIO{slash}CN5{slash}RB3-Pad13)") (class "Default")
      (node (ref "U2") (pin "13") (pinfunction "AN3/C2INA/VPIO/CN5/RB3_13") (pintype "bidirectional"))
    )
    (net (code "120") (name "unconnected-(U2-C3INA{slash}SESSEND{slash}CN16{slash}RD7-Pad55)") (class "Default")
      (node (ref "U2") (pin "55") (pinfunction "C3INA/SESSEND/CN16/RD7_55") (pintype "bidirectional"))
    )
    (net (code "121") (name "unconnected-(U2-C3INB{slash}CN15{slash}RD6-Pad54)") (class "Default")
      (node (ref "U2") (pin "54") (pinfunction "C3INB/CN15/RD6_54") (pintype "bidirectional"))
    )
    (net (code "122") (name "unconnected-(U2-DMH{slash}RP11{slash}INT0{slash}CN49{slash}RD0-Pad46)") (class "Default")
      (node (ref "U2") (pin "46") (pinfunction "DMH/RP11/INT0/CN49/RD0_46") (pintype "bidirectional"))
    )
    (net (code "123") (name "unconnected-(U2-DPH{slash}RP23{slash}CN51{slash}RD2-Pad50)") (class "Default")
      (node (ref "U2") (pin "50") (pinfunction "DPH/RP23/CN51/RD2_50") (pintype "bidirectional"))
    )
    (net (code "124") (name "unconnected-(U2-RTCC{slash}DMLN{slash}RP2{slash}CN53{slash}RD8-Pad42)") (class "Default")
      (node (ref "U2") (pin "42") (pinfunction "RTCC/DMLN/RP2/CN53/RD8_42") (pintype "bidirectional"))
    )
    (net (code "125") (name "unconnected-(U2-SOSCI{slash}C3IND{slash}CN1{slash}RC13-Pad47)") (class "Default")
      (node (ref "U2") (pin "47") (pinfunction "SOSCI/C3IND/CN1/RC13_47") (pintype "bidirectional"))
    )
    (net (code "126") (name "unconnected-(U2-SOSCO{slash}SCLKI{slash}T1CK{slash}C3INC{slash}RPI37{slash}CN0{slash}RC14-Pad48)") (class "Default")
      (node (ref "U2") (pin "48") (pinfunction "SOSCO/SCLKI/T1CK/C3INC/RPI37/CN0/RC14_48") (pintype "bidirectional"))
    )
  )
)
